# USB.net
KiCad netlist of a schematic drawn in Altium Designer
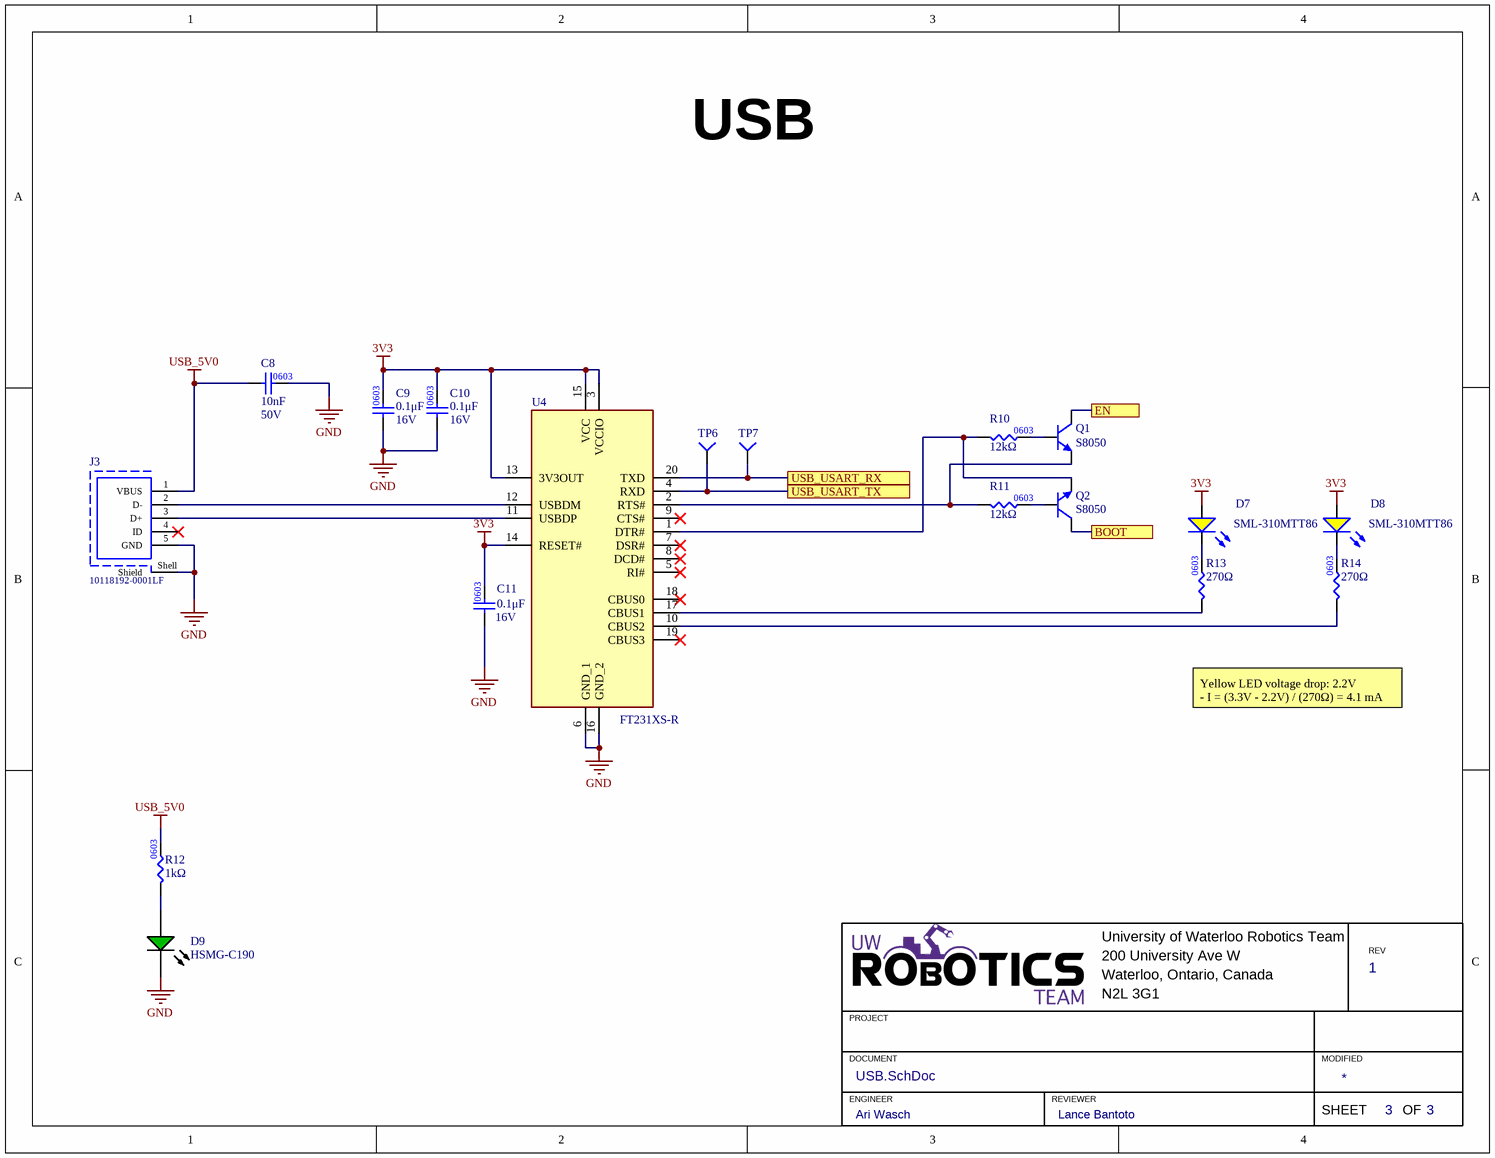
[diagram p0: USB.SchDoc]

(export (version "E")
  (design (tool "Eeschema 10.0.6"))
  (components
    (comp (ref "C8")
      (value "10nF")
      (footprint "CAP0603")
      (description "CAP CER 10nF 50V X7R 0603")
      (fields (field (name "VOLTAGE RATING") "50V") (field (name "Comment") "CAP_10nF_50V_0603"))
      (libsource (lib "UWRT_Schematic_Library_2020") (part "CAP_10nF_50V_0603"))
    )
    (comp (ref "C9")
      (value "0.1μF")
      (footprint "CAP0603")
      (description "CAP CER 0.1UF 16V X7R 0603")
      (fields (field (name "VOLTAGE RATING") "16V") (field (name "Comment") "CAP_0.1uF_16V_0603"))
      (libsource (lib "UWRT_Schematic_Library_2020") (part "CAP_0.1uF_16V_0603"))
    )
    (comp (ref "C10")
      (value "0.1μF")
      (footprint "CAP0603")
      (description "CAP CER 0.1UF 16V X7R 0603")
      (fields (field (name "VOLTAGE RATING") "16V") (field (name "Comment") "CAP_0.1uF_16V_0603"))
      (libsource (lib "UWRT_Schematic_Library_2020") (part "CAP_0.1uF_16V_0603"))
    )
    (comp (ref "C11")
      (value "0.1μF")
      (footprint "CAP0603")
      (description "CAP CER 0.1UF 16V X7R 0603")
      (fields (field (name "VOLTAGE RATING") "16V") (field (name "Comment") "CAP_0.1uF_16V_0603"))
      (libsource (lib "UWRT_Schematic_Library_2020") (part "CAP_0.1uF_16V_0603"))
    )
    (comp (ref "D7")
      (value "LED_YELLOW")
      (footprint "LED_0805_YELLOW")
      (description "LED YELLOW DIFFUSED 0805 SMD")
      (fields (field (name "MANUFACTURER PART NUMBER 1") "SML-310MTT86"))
      (libsource (lib "UWRT_Schematic_Library_2020") (part "LED_YELLOW"))
    )
    (comp (ref "D8")
      (value "LED_YELLOW")
      (footprint "LED_0805_YELLOW")
      (description "LED YELLOW DIFFUSED 0805 SMD")
      (fields (field (name "MANUFACTURER PART NUMBER 1") "SML-310MTT86"))
      (libsource (lib "UWRT_Schematic_Library_2020") (part "LED_YELLOW"))
    )
    (comp (ref "D9")
      (value "HSMG-C190")
      (footprint "AVAG-HSMX-C190_V")
      (description "Chip LED, Green, 2.2 V, -40 to 85 degC, 2-Pin SMD, RoHS, Tape and Reel")
      (libsource (lib "Altium Content Vault") (part "LED-GREEN-AK-2"))
    )
    (comp (ref "J3")
      (value "10118192-0001LF")
      (footprint "629105136821")
      (description "CONN RCPT USB2.0 MICRO B SMD R/A")
      (fields (field (name "MANUFACTURER") "Amphenol ICC"))
      (libsource (lib "UWRT_Schematic_Library_2020") (part "WE 629105136821"))
    )
    (comp (ref "Q1")
      (value "NPN_25V_500mA")
      (footprint "SOT23-3")
      (description "TRANS NPN 20V 0.5A SOT23")
      (fields (field (name "MANUFACTURER PART NUMBER 1") "S8050"))
      (libsource (lib "UWRT_Schematic_Library_2020") (part "NPN_25V_500mA"))
    )
    (comp (ref "Q2")
      (value "NPN_25V_500mA")
      (footprint "SOT23-3")
      (description "TRANS NPN 20V 0.5A SOT23")
      (fields (field (name "MANUFACTURER PART NUMBER 1") "S8050"))
      (libsource (lib "UWRT_Schematic_Library_2020") (part "NPN_25V_500mA"))
    )
    (comp (ref "R10")
      (value "12kΩ")
      (footprint "RESC0603")
      (description "RES 12K OHM 1% 1/10W 0603")
      (fields (field (name "POWER") "0.1W") (field (name "TOLERANCE") "1%"))
      (libsource (lib "UWRT_Schematic_Library_2020") (part "RES_12kΩ_0603_1%"))
    )
    (comp (ref "R11")
      (value "12kΩ")
      (footprint "RESC0603")
      (description "RES 12K OHM 1% 1/10W 0603")
      (fields (field (name "POWER") "0.1W") (field (name "TOLERANCE") "1%"))
      (libsource (lib "UWRT_Schematic_Library_2020") (part "RES_12kΩ_0603_1%"))
    )
    (comp (ref "R12")
      (value "1kΩ")
      (footprint "RES0603")
      (description "RES 1K OHM 5% 1/10W 0603")
      (fields (field (name "Comment") "RES_1kΩ_0603_5%"))
      (libsource (lib "UWRT_Schematic_Library_2020") (part "RES_1kΩ_0603_5%"))
    )
    (comp (ref "R13")
      (value "270Ω")
      (footprint "RES0603")
      (description "RES 270 OHM 1% 1/10W 0603")
      (fields (field (name "TOLERANCE") "±1%") (field (name "POWER") "0.1W"))
      (libsource (lib "UWRT_Schematic_Library_2020") (part "RES_270Ω_0603_1%"))
    )
    (comp (ref "R14")
      (value "270Ω")
      (footprint "RES0603")
      (description "RES 270 OHM 1% 1/10W 0603")
      (fields (field (name "TOLERANCE") "±1%") (field (name "POWER") "0.1W"))
      (libsource (lib "UWRT_Schematic_Library_2020") (part "RES_270Ω_0603_1%"))
    )
    (comp (ref "TP6")
      (value "TESTPOINT_1MM_SQUARE")
      (footprint "TESTPOINT_SQUARE_1MM")
      (description "TESTPOINT 1MM SQUARE")
      (libsource (lib "UWRT_Schematic_Library_2020") (part "TESTPOINT_1MM_SQUARE"))
    )
    (comp (ref "TP7")
      (value "TESTPOINT_1MM_SQUARE")
      (footprint "TESTPOINT_SQUARE_1MM")
      (description "TESTPOINT 1MM SQUARE")
      (libsource (lib "UWRT_Schematic_Library_2020") (part "TESTPOINT_1MM_SQUARE"))
    )
    (comp (ref "U4")
      (value "FT231XS-R")
      (footprint "SamacSys:SOP64P599X175-20N")
      (description "Integrated Circuit")
      (fields (field (name "MOUSER PART NUMBER") "895-FT231XS-R"))
      (libsource (lib "*") (part "FT231XS-R"))
    )
  )
  (nets
    (net (code "1") (name "/BOOT") (class "Default")
      (node (ref "Q2") (pin "3") (pinfunction "C_3") (pintype "passive"))
    )
    (net (code "2") (name "/EN") (class "Default")
      (node (ref "Q1") (pin "3") (pinfunction "C_3") (pintype "passive"))
    )
    (net (code "3") (name "/USB_USART_RX") (class "Default")
      (node (ref "TP7") (pin "1") (pinfunction "=value_1") (pintype "passive"))
      (node (ref "U4") (pin "20") (pinfunction "TXD_20") (pintype "passive"))
    )
    (net (code "4") (name "/USB_USART_TX") (class "Default")
      (node (ref "TP6") (pin "1") (pinfunction "=value_1") (pintype "passive"))
      (node (ref "U4") (pin "4") (pinfunction "RXD_4") (pintype "passive"))
    )
    (net (code "5") (name "3V3") (class "Default")
      (node (ref "C10") (pin "2") (pinfunction "2_2") (pintype "passive"))
      (node (ref "C11") (pin "2") (pinfunction "2_2") (pintype "passive"))
      (node (ref "C9") (pin "2") (pinfunction "2_2") (pintype "passive"))
      (node (ref "D7") (pin "1") (pinfunction "A_1") (pintype "passive"))
      (node (ref "D8") (pin "1") (pinfunction "A_1") (pintype "passive"))
      (node (ref "U4") (pin "13") (pinfunction "3V3OUT_13") (pintype "passive"))
      (node (ref "U4") (pin "14") (pinfunction "RESET#_14") (pintype "passive"))
      (node (ref "U4") (pin "15") (pinfunction "VCC_15") (pintype "passive"))
      (node (ref "U4") (pin "3") (pinfunction "VCCIO_3") (pintype "passive"))
    )
    (net (code "6") (name "GND") (class "Default")
      (node (ref "C10") (pin "1") (pinfunction "1_1") (pintype "passive"))
      (node (ref "C11") (pin "1") (pinfunction "1_1") (pintype "passive"))
      (node (ref "C8") (pin "2") (pinfunction "2_2") (pintype "passive"))
      (node (ref "C9") (pin "1") (pinfunction "1_1") (pintype "passive"))
      (node (ref "D9") (pin "2") (pinfunction "K_2") (pintype "passive"))
      (node (ref "J3") (pin "5") (pinfunction "GND_5") (pintype "passive"))
      (node (ref "J3") (pin "Shell") (pinfunction "Shield_Shell") (pintype "passive"))
      (node (ref "U4") (pin "16") (pinfunction "GND_2_16") (pintype "passive"))
      (node (ref "U4") (pin "6") (pinfunction "GND_1_6") (pintype "passive"))
    )
    (net (code "7") (name "Net-(D7-K)") (class "Default")
      (node (ref "D7") (pin "2") (pinfunction "K_2") (pintype "passive"))
      (node (ref "R13") (pin "2") (pinfunction "2_2") (pintype "passive"))
    )
    (net (code "8") (name "Net-(D8-K)") (class "Default")
      (node (ref "D8") (pin "2") (pinfunction "K_2") (pintype "passive"))
      (node (ref "R14") (pin "2") (pinfunction "2_2") (pintype "passive"))
    )
    (net (code "9") (name "Net-(D9-A)") (class "Default")
      (node (ref "D9") (pin "1") (pinfunction "A_1") (pintype "passive"))
      (node (ref "R12") (pin "1") (pinfunction "1_1") (pintype "passive"))
    )
    (net (code "10") (name "Net-(J3-D+)") (class "Default")
      (node (ref "J3") (pin "3") (pinfunction "D+_3") (pintype "passive"))
      (node (ref "U4") (pin "11") (pinfunction "USBDP_11") (pintype "passive"))
    )
    (net (code "11") (name "Net-(J3-D-)") (class "Default")
      (node (ref "J3") (pin "2") (pinfunction "D-_2") (pintype "passive"))
      (node (ref "U4") (pin "12") (pinfunction "USBDM_12") (pintype "passive"))
    )
    (net (code "12") (name "Net-(Q1-B)") (class "Default")
      (node (ref "Q1") (pin "1") (pinfunction "B_1") (pintype "passive"))
      (node (ref "R10") (pin "2") (pinfunction "2_2") (pintype "passive"))
    )
    (net (code "13") (name "Net-(Q1-E)") (class "Default")
      (node (ref "Q1") (pin "2") (pinfunction "E_2") (pintype "passive"))
      (node (ref "R11") (pin "1") (pinfunction "1_1") (pintype "passive"))
      (node (ref "U4") (pin "2") (pinfunction "RTS#_2") (pintype "passive"))
    )
    (net (code "14") (name "Net-(Q2-B)") (class "Default")
      (node (ref "Q2") (pin "1") (pinfunction "B_1") (pintype "passive"))
      (node (ref "R11") (pin "2") (pinfunction "2_2") (pintype "passive"))
    )
    (net (code "15") (name "Net-(Q2-E)") (class "Default")
      (node (ref "Q2") (pin "2") (pinfunction "E_2") (pintype "passive"))
      (node (ref "R10") (pin "1") (pinfunction "1_1") (pintype "passive"))
      (node (ref "U4") (pin "1") (pinfunction "DTR#_1") (pintype "passive"))
    )
    (net (code "16") (name "Net-(U4-CBUS1)") (class "Default")
      (node (ref "R13") (pin "1") (pinfunction "1_1") (pintype "passive"))
      (node (ref "U4") (pin "17") (pinfunction "CBUS1_17") (pintype "passive"))
    )
    (net (code "17") (name "Net-(U4-CBUS2)") (class "Default")
      (node (ref "R14") (pin "1") (pinfunction "1_1") (pintype "passive"))
      (node (ref "U4") (pin "10") (pinfunction "CBUS2_10") (pintype "passive"))
    )
    (net (code "18") (name "USB_5V0") (class "Default")
      (node (ref "C8") (pin "1") (pinfunction "1_1") (pintype "passive"))
      (node (ref "J3") (pin "1") (pinfunction "VBUS_1") (pintype "passive"))
      (node (ref "R12") (pin "2") (pinfunction "2_2") (pintype "passive"))
    )
    (net (code "19") (name "unconnected-(J3-ID-Pad4)") (class "Default")
      (node (ref "J3") (pin "4") (pinfunction "ID_4") (pintype "passive+no_connect"))
    )
    (net (code "20") (name "unconnected-(U4-CBUS0-Pad18)") (class "Default")
      (node (ref "U4") (pin "18") (pinfunction "CBUS0_18") (pintype "passive+no_connect"))
    )
    (net (code "21") (name "unconnected-(U4-CBUS3-Pad19)") (class "Default")
      (node (ref "U4") (pin "19") (pinfunction "CBUS3_19") (pintype "passive+no_connect"))
    )
    (net (code "22") (name "unconnected-(U4-CTS#-Pad9)") (class "Default")
      (node (ref "U4") (pin "9") (pinfunction "CTS#_9") (pintype "passive+no_connect"))
    )
    (net (code "23") (name "unconnected-(U4-DCD#-Pad8)") (class "Default")
      (node (ref "U4") (pin "8") (pinfunction "DCD#_8") (pintype "passive+no_connect"))
    )
    (net (code "24") (name "unconnected-(U4-DSR#-Pad7)") (class "Default")
      (node (ref "U4") (pin "7") (pinfunction "DSR#_7") (pintype "passive+no_connect"))
    )
    (net (code "25") (name "unconnected-(U4-RI#-Pad5)") (class "Default")
      (node (ref "U4") (pin "5") (pinfunction "RI#_5") (pintype "passive+no_connect"))
    )
  )
)
